# gameboyzero-split-bottom.net
KiCad netlist of a schematic drawn in EAGLE
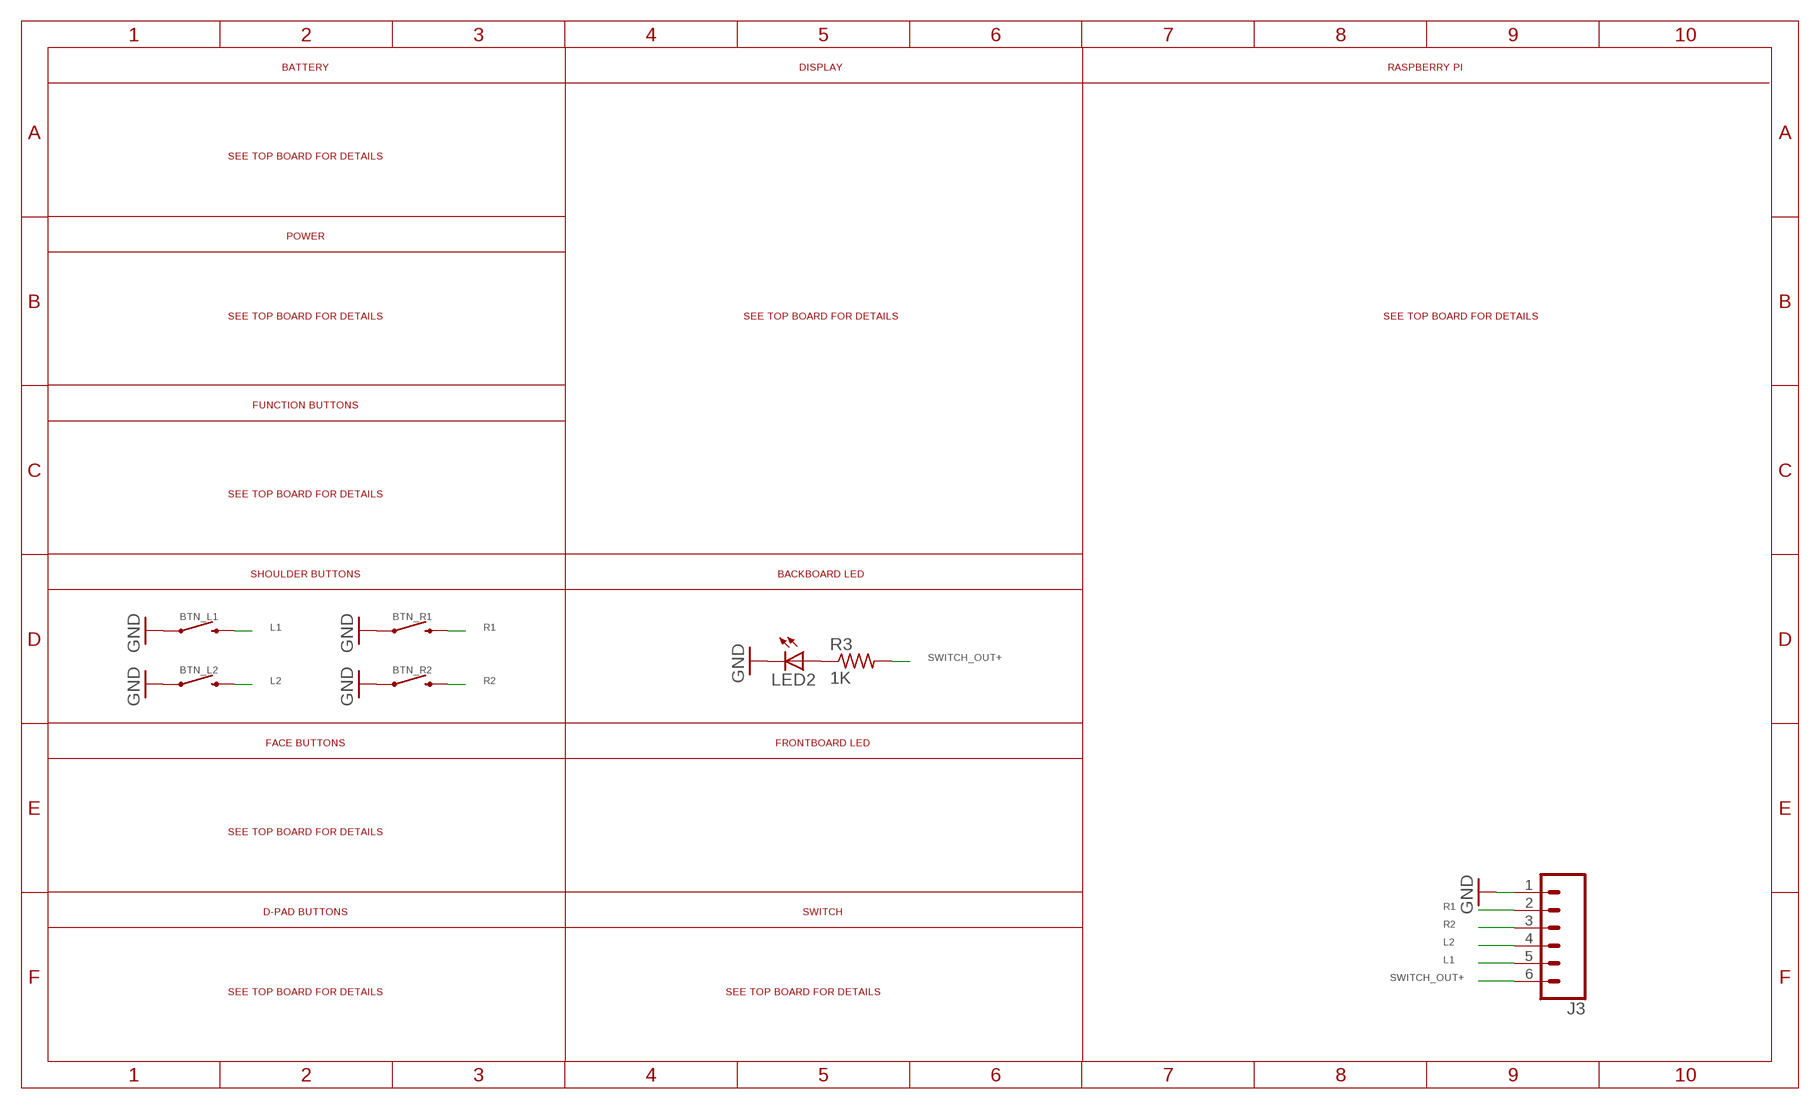
[diagram p0: schematic, sheet 1]

(export (version "E")
  (design (tool "Eeschema 10.0.6"))
  (components
    (comp (ref "BTN_L1")
      (value "MOMENTARY-SWITCH-SPST-SMD-12MM")
      (footprint "eagle-import:TACTILE_SWITCH_SMD_12MM")
      (libsource (lib "eagle-import") (part "MOMENTARY-SWITCH-SPST-SMD-12MM"))
    )
    (comp (ref "BTN_L2")
      (value "MOMENTARY-SWITCH-SPST-SMD-12MM")
      (footprint "eagle-import:TACTILE_SWITCH_SMD_12MM")
      (libsource (lib "eagle-import") (part "MOMENTARY-SWITCH-SPST-SMD-12MM"))
    )
    (comp (ref "BTN_R1")
      (value "MOMENTARY-SWITCH-SPST-SMD-12MM")
      (footprint "eagle-import:TACTILE_SWITCH_SMD_12MM")
      (libsource (lib "eagle-import") (part "MOMENTARY-SWITCH-SPST-SMD-12MM"))
    )
    (comp (ref "BTN_R2")
      (value "MOMENTARY-SWITCH-SPST-SMD-12MM")
      (footprint "eagle-import:TACTILE_SWITCH_SMD_12MM")
      (libsource (lib "eagle-import") (part "MOMENTARY-SWITCH-SPST-SMD-12MM"))
    )
    (comp (ref "J3")
      (value "CONN_06SILK_FEMALE_PTH")
      (footprint "eagle-import:1X06")
      (libsource (lib "eagle-import") (part "CONN_06SILK_FEMALE_PTH"))
    )
    (comp (ref "LED2")
      (value "LEDCHIPLED_0805")
      (footprint "eagle-import:CHIPLED_0805")
      (libsource (lib "eagle-import") (part "LEDCHIPLED_0805"))
    )
    (comp (ref "R3")
      (value "1K")
      (footprint "eagle-import:R0805")
      (libsource (lib "eagle-import") (part "R-US_R0805"))
    )
  )
  (nets
    (net (code "1") (name "/L1") (class "Default")
      (node (ref "BTN_L1") (pin "3") (pinfunction "2_3") (pintype "passive"))
      (node (ref "J3") (pin "5") (pinfunction "5_5") (pintype "passive"))
    )
    (net (code "2") (name "/L2") (class "Default")
      (node (ref "BTN_L2") (pin "3") (pinfunction "2_3") (pintype "passive"))
      (node (ref "J3") (pin "4") (pinfunction "4_4") (pintype "passive"))
    )
    (net (code "3") (name "/R1") (class "Default")
      (node (ref "BTN_R1") (pin "3") (pinfunction "2_3") (pintype "passive"))
      (node (ref "J3") (pin "2") (pinfunction "2_2") (pintype "passive"))
    )
    (net (code "4") (name "/R2") (class "Default")
      (node (ref "BTN_R2") (pin "3") (pinfunction "2_3") (pintype "passive"))
      (node (ref "J3") (pin "3") (pinfunction "3_3") (pintype "passive"))
    )
    (net (code "5") (name "/SWITCH_OUT+") (class "Default")
      (node (ref "J3") (pin "6") (pinfunction "6_6") (pintype "passive"))
      (node (ref "R3") (pin "2") (pinfunction "2_2") (pintype "passive"))
    )
    (net (code "6") (name "GND") (class "Default")
      (node (ref "BTN_L1") (pin "1") (pinfunction "1_1") (pintype "passive"))
      (node (ref "BTN_L2") (pin "1") (pinfunction "1_1") (pintype "passive"))
      (node (ref "BTN_R1") (pin "1") (pinfunction "1_1") (pintype "passive"))
      (node (ref "BTN_R2") (pin "1") (pinfunction "1_1") (pintype "passive"))
      (node (ref "J3") (pin "1") (pinfunction "1_1") (pintype "passive"))
      (node (ref "LED2") (pin "C") (pinfunction "C_C") (pintype "passive"))
    )
    (net (code "7") (name "Net-(LED2-PadA)") (class "Default")
      (node (ref "LED2") (pin "A") (pinfunction "A_A") (pintype "passive"))
      (node (ref "R3") (pin "1") (pinfunction "1_1") (pintype "passive"))
    )
  )
)
